# Rotary_Dial_v1_0.net
KiCad netlist of a schematic drawn in EAGLE
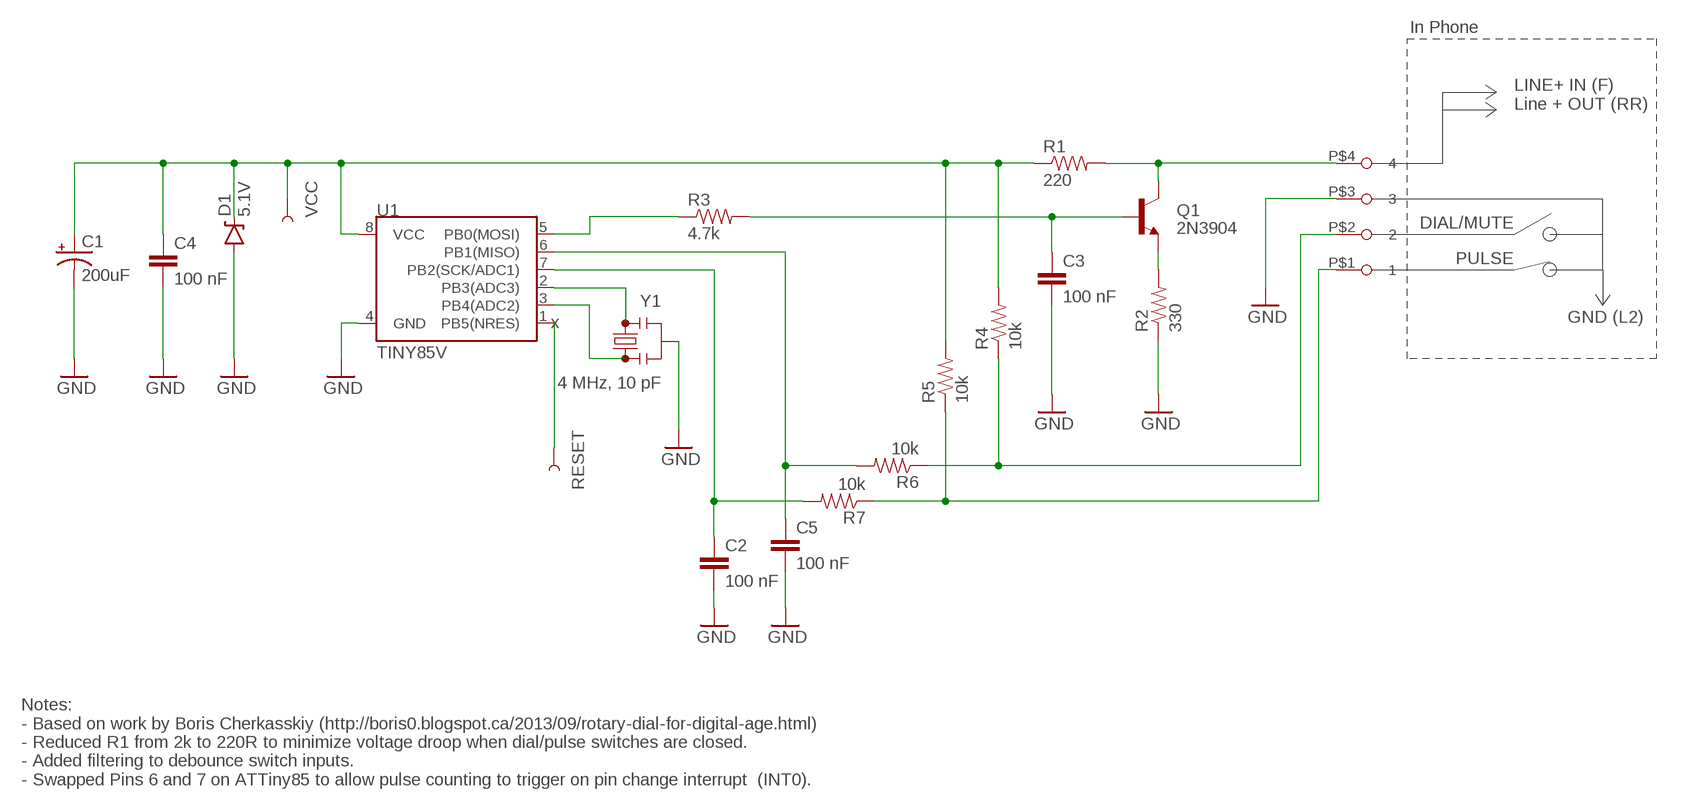
[diagram p0: schematic, sheet 1]

(export (version "E")
  (design (tool "Eeschema 10.0.6"))
  (components
    (comp (ref "C1")
      (value "200uF")
      (footprint "eagle-import:CPOL-RADIAL-100UF-25V")
      (libsource (lib "eagle-import") (part "100UF-25V-20%(PTH)"))
    )
    (comp (ref "C2")
      (value "100 nF")
      (footprint "eagle-import:CAP-PTH-SMALL")
      (libsource (lib "eagle-import") (part "CAPPTH"))
    )
    (comp (ref "C3")
      (value "100 nF")
      (footprint "eagle-import:CAP-PTH-SMALL")
      (libsource (lib "eagle-import") (part "CAPPTH"))
    )
    (comp (ref "C4")
      (value "100 nF")
      (footprint "eagle-import:CAP-PTH-SMALL")
      (libsource (lib "eagle-import") (part "CAPPTH"))
    )
    (comp (ref "C5")
      (value "100 nF")
      (footprint "eagle-import:CAP-PTH-SMALL")
      (libsource (lib "eagle-import") (part "CAPPTH"))
    )
    (comp (ref "D1")
      (value "5.1V")
      (footprint "eagle-import:DIODE-ZENER")
      (libsource (lib "eagle-import") (part "DIODE-ZENERPTH"))
    )
    (comp (ref "J1")
      (value "SCREW_TERMINAL_4")
      (footprint "eagle-import:.325_TERMINAL_4-PIN")
      (libsource (lib "eagle-import") (part "SCREW_TERMINAL_4"))
    )
    (comp (ref "Q1")
      (value "2N3904")
      (footprint "eagle-import:TO-92-AMMO")
      (libsource (lib "eagle-import") (part "TRANSISTOR_NPNTO-92-AMMO"))
    )
    (comp (ref "R1")
      (value "220")
      (footprint "eagle-import:AXIAL-0.1")
      (libsource (lib "eagle-import") (part "RESISTORPTH-1/4W-VERT"))
    )
    (comp (ref "R2")
      (value "330")
      (footprint "eagle-import:AXIAL-0.1")
      (libsource (lib "eagle-import") (part "RESISTORPTH-1/4W-VERT"))
    )
    (comp (ref "R3")
      (value "4.7k")
      (footprint "eagle-import:AXIAL-0.1")
      (libsource (lib "eagle-import") (part "RESISTORPTH-1/4W-VERT"))
    )
    (comp (ref "R4")
      (value "10k")
      (footprint "eagle-import:AXIAL-0.1")
      (libsource (lib "eagle-import") (part "RESISTORPTH-1/4W-VERT"))
    )
    (comp (ref "R5")
      (value "10k")
      (footprint "eagle-import:AXIAL-0.1")
      (libsource (lib "eagle-import") (part "RESISTORPTH-1/4W-VERT"))
    )
    (comp (ref "R6")
      (value "10k")
      (footprint "eagle-import:AXIAL-0.1")
      (libsource (lib "eagle-import") (part "RESISTORPTH-1/4W-VERT"))
    )
    (comp (ref "R7")
      (value "10k")
      (footprint "eagle-import:AXIAL-0.1")
      (libsource (lib "eagle-import") (part "RESISTORPTH-1/4W-VERT"))
    )
    (comp (ref "RESET")
      (value "TEST-POINTTP_15TH_THRU")
      (footprint "eagle-import:TP_15TH")
      (libsource (lib "eagle-import") (part "TEST-POINTTP_15TH_THRU"))
    )
    (comp (ref "U1")
      (value "TINY85V")
      (footprint "eagle-import:DIP08")
      (libsource (lib "eagle-import") (part "ATTINY45TINY85-20-DIP"))
    )
    (comp (ref "VCC")
      (value "TEST-POINTTP_15TH_THRU")
      (footprint "eagle-import:TP_15TH")
      (libsource (lib "eagle-import") (part "TEST-POINTTP_15TH_THRU"))
    )
    (comp (ref "Y1")
      (value "4 MHz, 10 pF")
      (footprint "eagle-import:RESONATOR-PTH")
      (libsource (lib "eagle-import") (part "RESONATORPTH"))
    )
  )
  (nets
    (net (code "1") (name "GND") (class "Default")
      (node (ref "C1") (pin "2") (pinfunction "-_2") (pintype "passive"))
      (node (ref "C2") (pin "2") (pinfunction "2_2") (pintype "passive"))
      (node (ref "C3") (pin "2") (pinfunction "2_2") (pintype "passive"))
      (node (ref "C4") (pin "2") (pinfunction "2_2") (pintype "passive"))
      (node (ref "C5") (pin "2") (pinfunction "2_2") (pintype "passive"))
      (node (ref "D1") (pin "P$2") (pinfunction "A_P$2") (pintype "passive"))
      (node (ref "J1") (pin "P$3") (pinfunction "3_P$3") (pintype "bidirectional"))
      (node (ref "R2") (pin "P$1") (pinfunction "1_P$1") (pintype "passive"))
      (node (ref "U1") (pin "4") (pinfunction "GND_4") (pintype "bidirectional"))
      (node (ref "Y1") (pin "2") (pinfunction "2_2") (pintype "passive"))
    )
    (net (code "2") (name "Net-(C1-+)") (class "Default")
      (node (ref "C1") (pin "1") (pinfunction "+_1") (pintype "passive"))
      (node (ref "C4") (pin "1") (pinfunction "1_1") (pintype "passive"))
      (node (ref "D1") (pin "P$1") (pinfunction "C_P$1") (pintype "passive"))
      (node (ref "R1") (pin "P$1") (pinfunction "1_P$1") (pintype "passive"))
      (node (ref "R4") (pin "P$2") (pinfunction "2_P$2") (pintype "passive"))
      (node (ref "R5") (pin "P$2") (pinfunction "2_P$2") (pintype "passive"))
      (node (ref "U1") (pin "8") (pinfunction "VCC_8") (pintype "bidirectional"))
      (node (ref "VCC") (pin "P$1") (pinfunction "1_P$1") (pintype "bidirectional"))
    )
    (net (code "3") (name "Net-(J1-1)") (class "Default")
      (node (ref "J1") (pin "P$1") (pinfunction "1_P$1") (pintype "bidirectional"))
      (node (ref "R5") (pin "P$1") (pinfunction "1_P$1") (pintype "passive"))
      (node (ref "R7") (pin "P$1") (pinfunction "1_P$1") (pintype "passive"))
    )
    (net (code "4") (name "Net-(J1-2)") (class "Default")
      (node (ref "J1") (pin "P$2") (pinfunction "2_P$2") (pintype "bidirectional"))
      (node (ref "R4") (pin "P$1") (pinfunction "1_P$1") (pintype "passive"))
      (node (ref "R6") (pin "P$1") (pinfunction "1_P$1") (pintype "passive"))
    )
    (net (code "5") (name "Net-(J1-4)") (class "Default")
      (node (ref "J1") (pin "P$4") (pinfunction "4_P$4") (pintype "bidirectional"))
      (node (ref "Q1") (pin "3") (pinfunction "C_3") (pintype "passive"))
      (node (ref "R1") (pin "P$2") (pinfunction "2_P$2") (pintype "passive"))
    )
    (net (code "6") (name "Net-(Q1-B)") (class "Default")
      (node (ref "C3") (pin "1") (pinfunction "1_1") (pintype "passive"))
      (node (ref "Q1") (pin "2") (pinfunction "B_2") (pintype "passive"))
      (node (ref "R3") (pin "P$2") (pinfunction "2_P$2") (pintype "passive"))
    )
    (net (code "7") (name "Net-(Q1-E)") (class "Default")
      (node (ref "Q1") (pin "1") (pinfunction "E_1") (pintype "passive"))
      (node (ref "R2") (pin "P$2") (pinfunction "2_P$2") (pintype "passive"))
    )
    (net (code "8") (name "Net-(R3-1)") (class "Default")
      (node (ref "R3") (pin "P$1") (pinfunction "1_P$1") (pintype "passive"))
      (node (ref "U1") (pin "5") (pinfunction "PB0(MOSI)_5") (pintype "bidirectional"))
    )
    (net (code "9") (name "Net-(R6-2)") (class "Default")
      (node (ref "C5") (pin "1") (pinfunction "1_1") (pintype "passive"))
      (node (ref "R6") (pin "P$2") (pinfunction "2_P$2") (pintype "passive"))
      (node (ref "U1") (pin "6") (pinfunction "PB1(MISO)_6") (pintype "bidirectional"))
    )
    (net (code "10") (name "Net-(R7-2)") (class "Default")
      (node (ref "C2") (pin "1") (pinfunction "1_1") (pintype "passive"))
      (node (ref "R7") (pin "P$2") (pinfunction "2_P$2") (pintype "passive"))
      (node (ref "U1") (pin "7") (pinfunction "PB2(SCK/ADC1)_7") (pintype "bidirectional"))
    )
    (net (code "11") (name "Net-(RESET-1)") (class "Default")
      (node (ref "RESET") (pin "P$1") (pinfunction "1_P$1") (pintype "bidirectional"))
      (node (ref "U1") (pin "1") (pinfunction "PB5(NRES)_1") (pintype "bidirectional"))
    )
    (net (code "12") (name "Net-(U1-PB3(ADC3))") (class "Default")
      (node (ref "U1") (pin "2") (pinfunction "PB3(ADC3)_2") (pintype "bidirectional"))
      (node (ref "Y1") (pin "3") (pinfunction "3_3") (pintype "passive"))
    )
    (net (code "13") (name "Net-(U1-PB4(ADC2))") (class "Default")
      (node (ref "U1") (pin "3") (pinfunction "PB4(ADC2)_3") (pintype "bidirectional"))
      (node (ref "Y1") (pin "1") (pinfunction "1_1") (pintype "passive"))
    )
  )
)
